# TVP5150AM1.net
KiCad netlist of a schematic drawn in Altium Designer
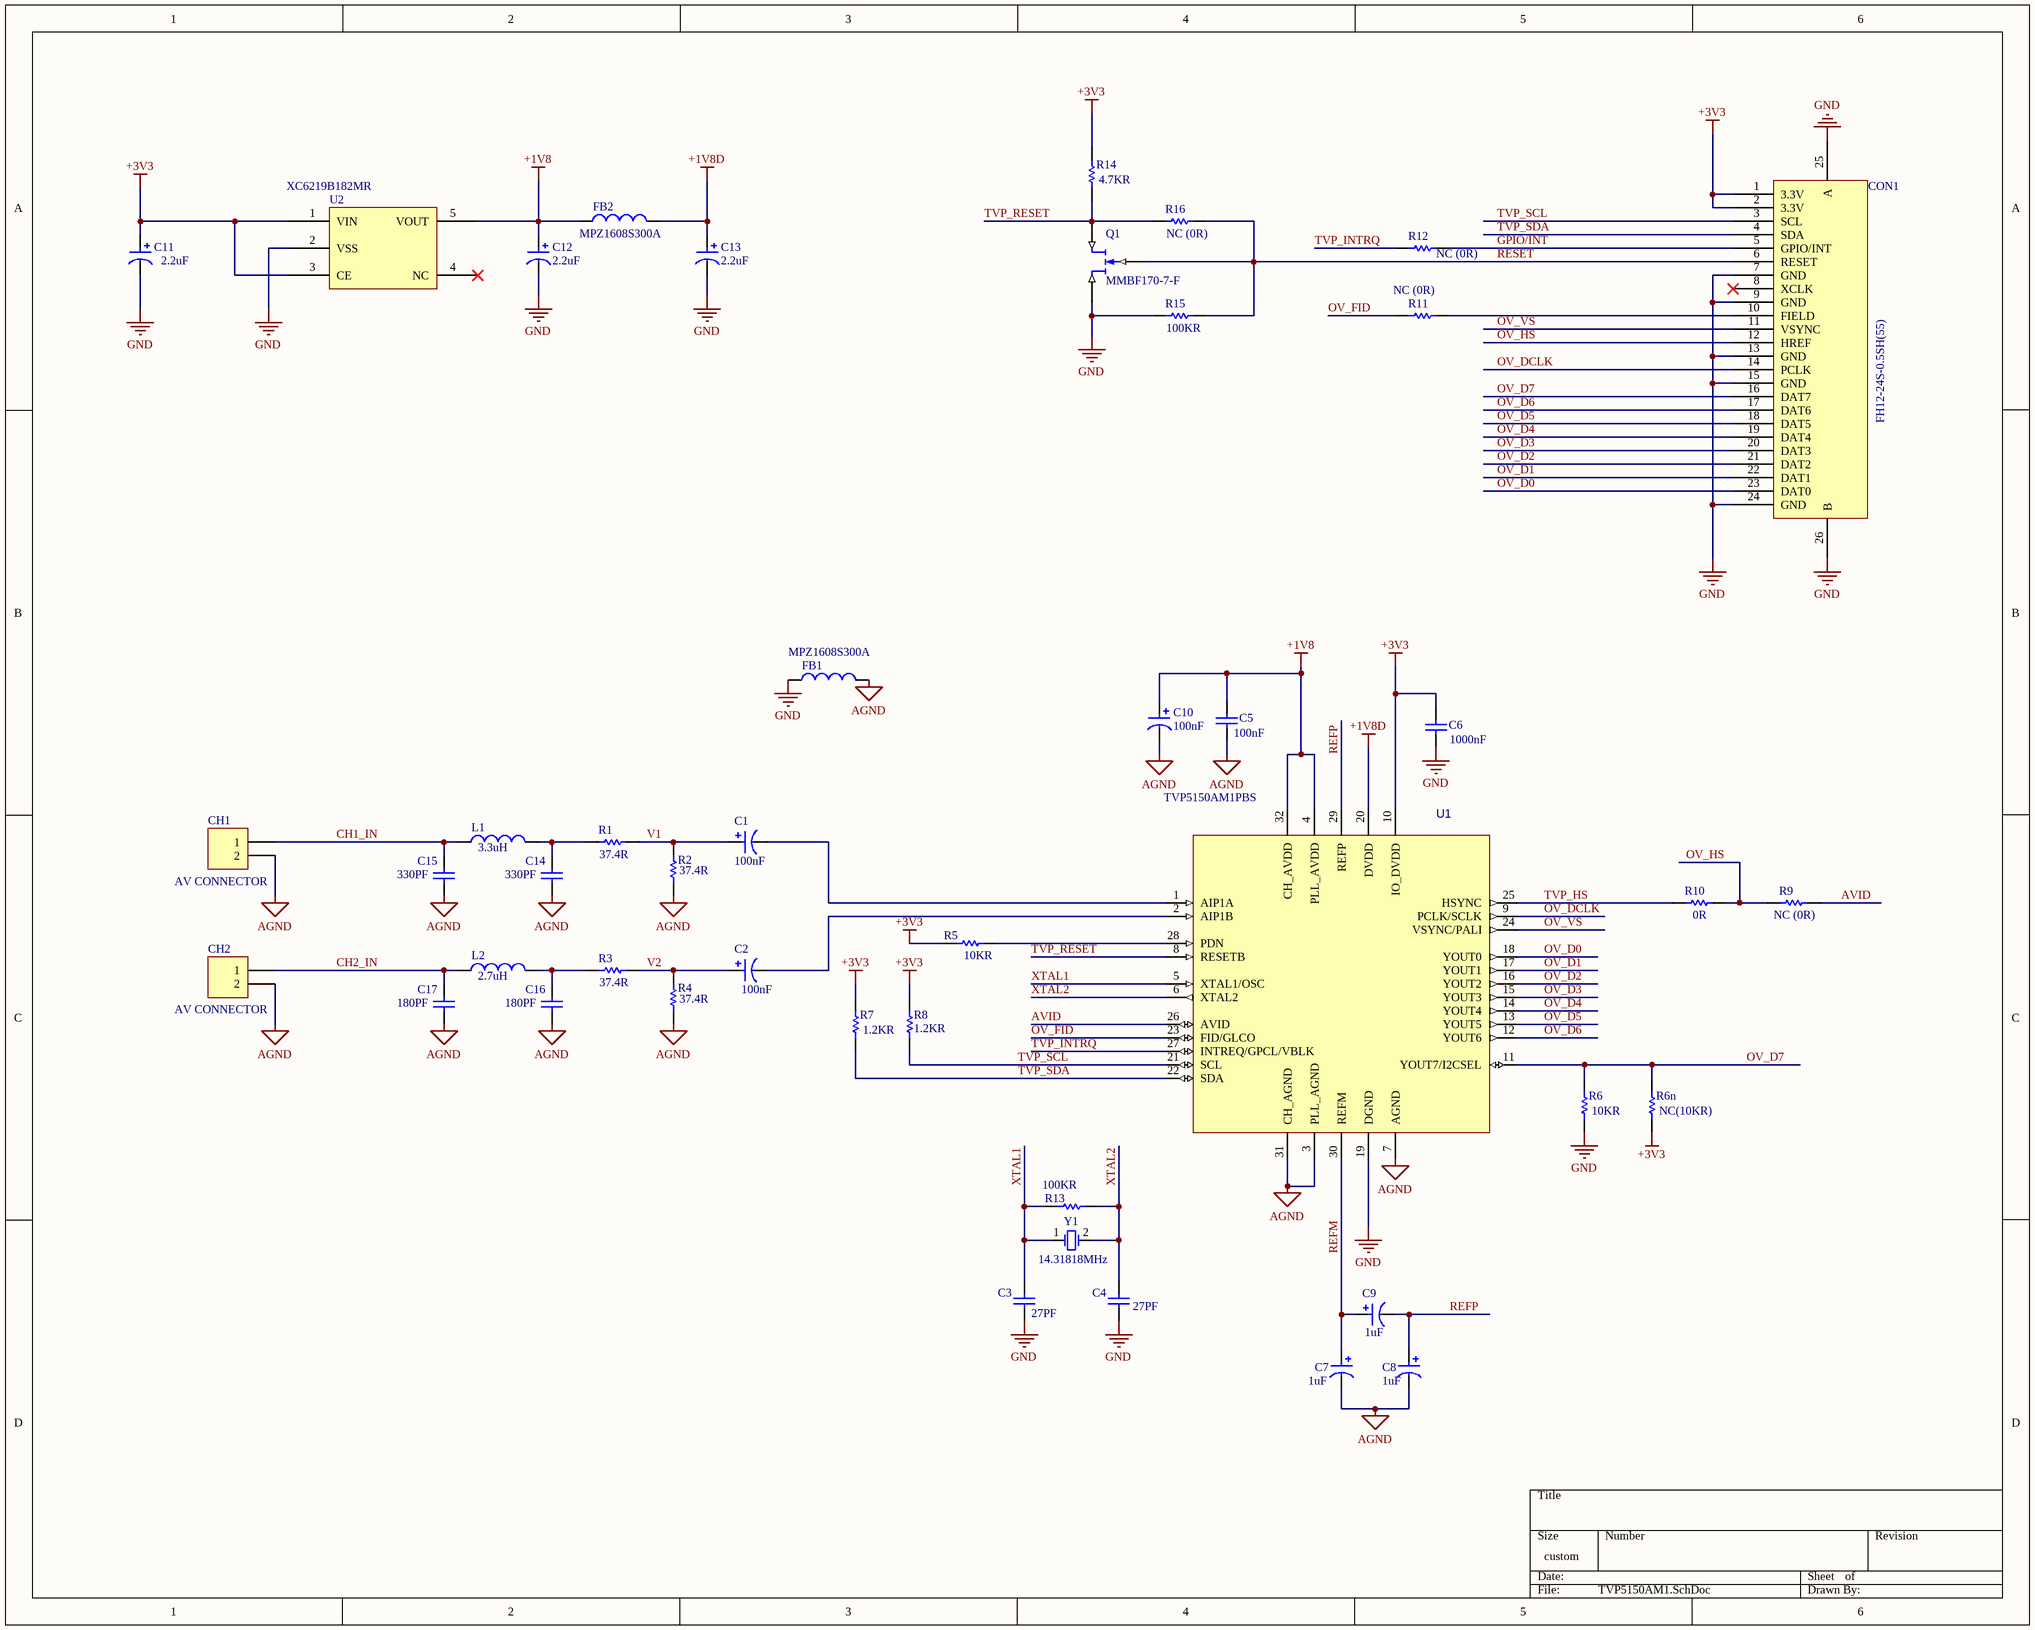
[diagram p0: TVP5150AM1.SchDoc]

(export (version "E")
  (design (tool "Eeschema 10.0.6"))
  (components
    (comp (ref "C1")
      (value "100nF")
      (footprint "C_1206 (3216 Metric)")
      (description "Chip Monolithic Ceramic Capacitor; SMD")
      (fields
        (field (name "MANUFACTURER") "Vishay or AVX Corporation")
        (field (name "PARTNUMBER") "100nF")
        (field (name "PUBLISHER") "Altium Limited")
      )
      (libsource (lib "Main_Lib") (part "Cap Pol SMD"))
    )
    (comp (ref "C2")
      (value "100nF")
      (footprint "C_1206 (3216 Metric)")
      (description "Chip Monolithic Ceramic Capacitor; SMD")
      (fields
        (field (name "MANUFACTURER") "Vishay or AVX Corporation")
        (field (name "PARTNUMBER") "100nF")
        (field (name "PUBLISHER") "Altium Limited")
      )
      (libsource (lib "Main_Lib") (part "Cap Pol SMD"))
    )
    (comp (ref "C3")
      (value "27PF")
      (footprint "C_0805 (2012 Metric)")
      (description "Chip Monolithic Ceramic Capacitor; SMD")
      (fields (field (name "PARTNUMBER") "27PF") (field (name "PUBLISHER") "Altium Limited"))
      (libsource (lib "Miscellaneous Devices") (part "Cap"))
    )
    (comp (ref "C4")
      (value "27PF")
      (footprint "C_0805 (2012 Metric)")
      (description "Chip Monolithic Ceramic Capacitor; SMD")
      (fields (field (name "PARTNUMBER") "27PF") (field (name "PUBLISHER") "Altium Limited"))
      (libsource (lib "Miscellaneous Devices") (part "Cap"))
    )
    (comp (ref "C5")
      (value "100nF")
      (footprint "C_0805 (2012 Metric)")
      (description "Chip Monolithic Ceramic Capacitor; SMD")
      (fields (field (name "PARTNUMBER") "100nF") (field (name "PUBLISHER") "Altium Limited"))
      (libsource (lib "Miscellaneous Devices") (part "Cap"))
    )
    (comp (ref "C6")
      (value "1000nF")
      (footprint "C_0805 (2012 Metric)")
      (description "Chip Monolithic Ceramic Capacitor; SMD")
      (fields (field (name "PARTNUMBER") "1000nF") (field (name "PUBLISHER") "Altium Limited"))
      (libsource (lib "Miscellaneous Devices") (part "Cap"))
    )
    (comp (ref "C7")
      (value "1uF")
      (footprint "C_1206 (3216 Metric)")
      (description "Chip Monolithic Ceramic Capacitor; SMD")
      (fields
        (field (name "MANUFACTURER") "Vishay or AVX Corporation")
        (field (name "PARTNUMBER") "1uF")
        (field (name "PUBLISHER") "Altium Limited")
      )
      (libsource (lib "") (part "Cap Pol SMD_1"))
    )
    (comp (ref "C8")
      (value "1uF")
      (footprint "C_1206 (3216 Metric)")
      (description "Chip Monolithic Ceramic Capacitor; SMD")
      (fields
        (field (name "MANUFACTURER") "Vishay or AVX Corporation")
        (field (name "PARTNUMBER") "1uF")
        (field (name "PUBLISHER") "Altium Limited")
      )
      (libsource (lib "") (part "Cap Pol SMD_1"))
    )
    (comp (ref "C9")
      (value "1uF")
      (footprint "C_1206 (3216 Metric)")
      (description "Chip Monolithic Ceramic Capacitor; SMD")
      (fields
        (field (name "MANUFACTURER") "Vishay or AVX Corporation")
        (field (name "PARTNUMBER") "1uF")
        (field (name "PUBLISHER") "Altium Limited")
      )
      (libsource (lib "Main_Lib") (part "Cap Pol SMD"))
    )
    (comp (ref "C10")
      (value "100nF")
      (footprint "C_1206 (3216 Metric)")
      (description "Chip Monolithic Ceramic Capacitor; SMD")
      (fields
        (field (name "MANUFACTURER") "Vishay or AVX Corporation")
        (field (name "PARTNUMBER") "100nF")
        (field (name "PUBLISHER") "Altium Limited")
      )
      (libsource (lib "") (part "Cap Pol SMD_1"))
    )
    (comp (ref "C11")
      (value "2.2uF")
      (footprint "Tantalum-A")
      (description "Tantalum SMD Capacitor")
      (fields
        (field (name "MANUFACTURER") "Vishay or AVX Corporation")
        (field (name "PARTNUMBER") "2.2uF")
        (field (name "PUBLISHER") "Altium Limited")
      )
      (libsource (lib "") (part "Cap Pol SMD_1"))
    )
    (comp (ref "C12")
      (value "2.2uF")
      (footprint "Tantalum-A")
      (description "Tantalum SMD Capacitor")
      (fields
        (field (name "MANUFACTURER") "Vishay or AVX Corporation")
        (field (name "PARTNUMBER") "2.2uF")
        (field (name "PUBLISHER") "Altium Limited")
      )
      (libsource (lib "") (part "Cap Pol SMD_1"))
    )
    (comp (ref "C13")
      (value "2.2uF")
      (footprint "Tantalum-A")
      (description "Tantalum SMD Capacitor")
      (fields
        (field (name "MANUFACTURER") "Vishay or AVX Corporation")
        (field (name "PART NUMBER") "2.2uF")
        (field (name "PUBLISHER") "Altium Limited")
      )
      (libsource (lib "") (part "Cap Pol SMD_1"))
    )
    (comp (ref "C14")
      (value "330PF")
      (footprint "C_0805 (2012 Metric)")
      (description "Chip Monolithic Ceramic Capacitor; SMD")
      (fields (field (name "PARTNUMBER") "330PF") (field (name "PUBLISHER") "Altium Limited"))
      (libsource (lib "Miscellaneous Devices") (part "Cap"))
    )
    (comp (ref "C15")
      (value "330PF")
      (footprint "C_0805 (2012 Metric)")
      (description "Chip Monolithic Ceramic Capacitor; SMD")
      (fields (field (name "PARTNUMBER") "330PF") (field (name "PUBLISHER") "Altium Limited"))
      (libsource (lib "Miscellaneous Devices") (part "Cap"))
    )
    (comp (ref "C16")
      (value "180PF")
      (footprint "C_0805 (2012 Metric)")
      (description "Chip Monolithic Ceramic Capacitor; SMD")
      (fields (field (name "PARTNUMBER") "180PF") (field (name "PUBLISHER") "Altium Limited"))
      (libsource (lib "Miscellaneous Devices") (part "Cap"))
    )
    (comp (ref "C17")
      (value "180PF")
      (footprint "C_0805 (2012 Metric)")
      (description "Chip Monolithic Ceramic Capacitor; SMD")
      (fields (field (name "PARTNUMBER") "180PF") (field (name "PUBLISHER") "Altium Limited"))
      (libsource (lib "Miscellaneous Devices") (part "Cap"))
    )
    (comp (ref "CH1")
      (value "AV CONNECTOR")
      (footprint "RCA-CONN")
      (description "Header, 2-Pin")
      (fields (field (name "PARTNUMBER") "AV CONNECTOR") (field (name "PUBLISHER") "Altium Limited"))
      (libsource (lib "Miscellaneous Connectors") (part "Header 2"))
    )
    (comp (ref "CH2")
      (value "AV CONNECTOR")
      (footprint "RCA-CONN")
      (description "Header, 2-Pin")
      (fields (field (name "PARTNUMBER") "AV CONNECTOR") (field (name "PUBLISHER") "Altium Limited"))
      (libsource (lib "Miscellaneous Connectors") (part "Header 2"))
    )
    (comp (ref "CON1")
      (value "24 PIN FFC CONNECTOR 0.5MM PITCH")
      (footprint "FH12-24S-0.5SH")
      (description "CONN FFC BOTTOM 24POS 0.50MM R/A")
      (fields
        (field (name "MANUFACTURER") "Hirose Electric Co Ltd")
        (field (name "MANUFACTURER PART NUMBER") "FH12-24S-0.5SH(55)")
        (field (name "PARTNUMBER") "FH12-24S-0.5SH(55)")
      )
      (libsource (lib "TVP5150AM1") (part "CSI DVP CAMERA CONNECTOR"))
    )
    (comp (ref "FB1")
      (value "MPZ1608S300A")
      (footprint "L_0805 (2012 Metric)")
      (description "FERRITE BEAD 30 OHM 0603 1LN")
      (fields
        (field (name "PARTNUMBER") "MPZ1608S300A")
        (field (name "MANUFACTURER PART NUMBER") "MPZ1608S300ATAH0")
        (field (name "PUBLISHER") "Altium Limited")
      )
      (libsource (lib "Main_Lib") (part "Inductor"))
    )
    (comp (ref "FB2")
      (value "MPZ1608S300A")
      (footprint "L_0805 (2012 Metric)")
      (description "FERRITE BEAD 30 OHM 0603 1LN")
      (fields
        (field (name "PARTNUMBER") "MPZ1608S300A")
        (field (name "MANUFACTURER PART NUMBER") "MPZ1608S300ATAH0")
        (field (name "PUBLISHER") "Altium Limited")
      )
      (libsource (lib "Main_Lib") (part "Inductor"))
    )
    (comp (ref "L1")
      (value "3.3uH")
      (footprint "L_0805 (2012 Metric)")
      (description "FIXED IND 3.3UH 750MA 300 MOHM SMD")
      (fields (field (name "PARTNUMBER") "3.3uH") (field (name "PUBLISHER") "Altium Limited"))
      (libsource (lib "Main_Lib") (part "Inductor"))
    )
    (comp (ref "L2")
      (value "2.7uH")
      (footprint "L_0805 (2012 Metric)")
      (description "FIXED IND 2.7UH 750MA 300 MOHM SMD")
      (fields (field (name "PARTNUMBER") "2.7uH") (field (name "PUBLISHER") "Altium Limited"))
      (libsource (lib "Main_Lib") (part "Inductor"))
    )
    (comp (ref "Q1")
      (value "MMBF170-7-F")
      (footprint "SOT-23-3")
      (description "MOSFET N-CH 60V 500MA SOT23-3")
      (fields (field (name "MANUFACTURER") "Diodes Incorporated") (field (name "PARTNUMBER") "MMBF170-7-F"))
      (libsource (lib "Miscellaneous Devices") (part "MESFET-N"))
    )
    (comp (ref "R1")
      (value "37.4R")
      (footprint "R_0805 (2012 Metric)")
      (description "Resistor")
      (fields (field (name "PARTNUMBER") "37.4R") (field (name "PUBLISHER") "Altium Limited"))
      (libsource (lib "Miscellaneous Devices") (part "Res1"))
    )
    (comp (ref "R2")
      (value "37.4R")
      (footprint "R_0805 (2012 Metric)")
      (description "Resistor")
      (fields (field (name "PARTNUMBER") "37.4R") (field (name "PUBLISHER") "Altium Limited"))
      (libsource (lib "Miscellaneous Devices") (part "Res1"))
    )
    (comp (ref "R3")
      (value "37.4R")
      (footprint "R_0805 (2012 Metric)")
      (description "Resistor")
      (fields (field (name "PARTNUMBER") "37.4R") (field (name "PUBLISHER") "Altium Limited"))
      (libsource (lib "Miscellaneous Devices") (part "Res1"))
    )
    (comp (ref "R4")
      (value "37.4R")
      (footprint "R_0805 (2012 Metric)")
      (description "Resistor")
      (fields (field (name "PARTNUMBER") "37.4R") (field (name "PUBLISHER") "Altium Limited"))
      (libsource (lib "Miscellaneous Devices") (part "Res1"))
    )
    (comp (ref "R5")
      (value "10KR")
      (footprint "R_0805 (2012 Metric)")
      (description "Resistor")
      (fields (field (name "PARTNUMBER") "10KR") (field (name "PUBLISHER") "Altium Limited"))
      (libsource (lib "Miscellaneous Devices") (part "Res1"))
    )
    (comp (ref "R6")
      (value "10KR")
      (footprint "R_0805 (2012 Metric)")
      (description "Resistor")
      (fields (field (name "PARTNUMBER") "10KR") (field (name "PUBLISHER") "Altium Limited"))
      (libsource (lib "Miscellaneous Devices") (part "Res1"))
    )
    (comp (ref "R6n")
      (value "NC(10KR)")
      (footprint "R_0805 (2012 Metric)")
      (description "Resistor")
      (fields (field (name "PARTNUMBER") "NC(10KR)") (field (name "PUBLISHER") "Altium Limited"))
      (libsource (lib "Miscellaneous Devices") (part "Res1"))
    )
    (comp (ref "R7")
      (value "1.2KR")
      (footprint "R_0805 (2012 Metric)")
      (description "Resistor")
      (fields (field (name "PARTNUMBER") "1.2KR") (field (name "PUBLISHER") "Altium Limited"))
      (libsource (lib "Miscellaneous Devices") (part "Res1"))
    )
    (comp (ref "R8")
      (value "1.2KR")
      (footprint "R_0805 (2012 Metric)")
      (description "Resistor")
      (fields (field (name "PARTNUMBER") "1.2KR") (field (name "PUBLISHER") "Altium Limited"))
      (libsource (lib "Miscellaneous Devices") (part "Res1"))
    )
    (comp (ref "R9")
      (value "NC (0R)")
      (footprint "R_0805 (2012 Metric)")
      (description "Resistor")
      (fields (field (name "PARTNUMBER") "NC (0R)") (field (name "PUBLISHER") "Altium Limited"))
      (libsource (lib "Miscellaneous Devices") (part "Res1"))
    )
    (comp (ref "R10")
      (value "0R")
      (footprint "R_0805 (2012 Metric)")
      (description "Resistor")
      (fields (field (name "PARTNUMBER") "0R") (field (name "PUBLISHER") "Altium Limited"))
      (libsource (lib "Miscellaneous Devices") (part "Res1"))
    )
    (comp (ref "R11")
      (value "NC (0R)")
      (footprint "R_0805 (2012 Metric)")
      (description "Resistor")
      (fields (field (name "PARTNUMBER") "NC (0R)") (field (name "PUBLISHER") "Altium Limited"))
      (libsource (lib "Miscellaneous Devices") (part "Res1"))
    )
    (comp (ref "R12")
      (value "NC (0R)")
      (footprint "R_0805 (2012 Metric)")
      (description "Resistor")
      (fields (field (name "PARTNUMBER") "NC (0R)") (field (name "PUBLISHER") "Altium Limited"))
      (libsource (lib "Miscellaneous Devices") (part "Res1"))
    )
    (comp (ref "R13")
      (value "100KR")
      (footprint "R_0805 (2012 Metric)")
      (description "Resistor")
      (fields (field (name "PARTNUMBER") "100KR") (field (name "PUBLISHER") "Altium Limited"))
      (libsource (lib "Miscellaneous Devices") (part "Res1"))
    )
    (comp (ref "R14")
      (value "4.7KR")
      (footprint "R_0805 (2012 Metric)")
      (description "Resistor")
      (fields (field (name "PARTNUMBER") "4.7KR") (field (name "PUBLISHER") "Altium Limited"))
      (libsource (lib "Miscellaneous Devices") (part "Res1"))
    )
    (comp (ref "R15")
      (value "100KR")
      (footprint "R_0805 (2012 Metric)")
      (description "Resistor")
      (fields (field (name "PARTNUMBER") "100KR") (field (name "PUBLISHER") "Altium Limited"))
      (libsource (lib "Miscellaneous Devices") (part "Res1"))
    )
    (comp (ref "R16")
      (value "NC (0R)")
      (footprint "R_0805 (2012 Metric)")
      (description "Resistor")
      (fields (field (name "PARTNUMBER") "NC (0R)") (field (name "PUBLISHER") "Altium Limited"))
      (libsource (lib "Miscellaneous Devices") (part "Res1"))
    )
    (comp (ref "U1")
      (value "TVP5150AM1PBS")
      (footprint "PBS32")
      (description "Ultralow Power NTSC/PAL/SECAM 9-Bit Video Decoder with Robust Sync Detector, 32-Pin TQFP")
      (fields (field (name "PARTNUMBER") "TVP5150AM1PBS") (field (name "PUBLISHER") "Altium Limited"))
      (libsource (lib "TI Video Colour Decoder Circuit") (part "TVP5150AM1PBS"))
    )
    (comp (ref "U2")
      (value "XC6219B182MR")
      (footprint "SOT23-5")
      (description "300mA High Speed LDO Regulators with ON/OFF Switch")
      (fields (field (name "PARTNUMBER") "XC6219B182MR"))
      (libsource (lib "TVP5150AM1") (part "XC6219B182MR"))
    )
    (comp (ref "Y1")
      (value "14.31818MHz")
      (footprint "XTAL_S")
      (description "CRYSTAL 14.7456MHZ 18PF THRU")
      (fields
        (field (name "MANUFACTURER") "TXC CORPORATION")
        (field (name "PARTNUMBER") "14.31818MHz")
        (field (name "PUBLISHER") "Altium Limited")
      )
      (libsource (lib "Main_Lib") (part "XTAL"))
    )
  )
  (nets
    (net (code "1") (name "+1V8") (class "Default")
      (node (ref "C10") (pin "1") (pinfunction "1_1") (pintype "passive"))
      (node (ref "C12") (pin "1") (pinfunction "1_1") (pintype "passive"))
      (node (ref "C5") (pin "1") (pinfunction "1_1") (pintype "passive"))
      (node (ref "FB2") (pin "1") (pinfunction "1_1") (pintype "passive"))
      (node (ref "U1") (pin "32") (pinfunction "CH_AVDD_32") (pintype "power_in"))
      (node (ref "U1") (pin "4") (pinfunction "PLL_AVDD_4") (pintype "power_in"))
      (node (ref "U2") (pin "5") (pinfunction "VOUT_5") (pintype "passive"))
    )
    (net (code "2") (name "+1V8D") (class "Default")
      (node (ref "C13") (pin "1") (pinfunction "1_1") (pintype "passive"))
      (node (ref "FB2") (pin "2") (pinfunction "2_2") (pintype "passive"))
      (node (ref "U1") (pin "20") (pinfunction "DVDD_20") (pintype "power_in"))
    )
    (net (code "3") (name "+3V3") (class "Default")
      (node (ref "C11") (pin "1") (pinfunction "1_1") (pintype "passive"))
      (node (ref "C6") (pin "1") (pinfunction "1_1") (pintype "passive"))
      (node (ref "CON1") (pin "1") (pinfunction "3.3V_1") (pintype "passive"))
      (node (ref "CON1") (pin "2") (pinfunction "3.3V_2") (pintype "passive"))
      (node (ref "R14") (pin "1") (pinfunction "1_1") (pintype "passive"))
      (node (ref "R5") (pin "2") (pinfunction "2_2") (pintype "passive"))
      (node (ref "R6n") (pin "2") (pinfunction "2_2") (pintype "passive"))
      (node (ref "R7") (pin "1") (pinfunction "1_1") (pintype "passive"))
      (node (ref "R8") (pin "1") (pinfunction "1_1") (pintype "passive"))
      (node (ref "U1") (pin "10") (pinfunction "IO_DVDD_10") (pintype "power_in"))
      (node (ref "U2") (pin "1") (pinfunction "VIN_1") (pintype "passive"))
      (node (ref "U2") (pin "3") (pinfunction "CE_3") (pintype "passive"))
    )
    (net (code "4") (name "/AVID") (class "Default")
      (node (ref "R9") (pin "2") (pinfunction "2_2") (pintype "passive"))
      (node (ref "U1") (pin "26") (pinfunction "AVID_26") (pintype "bidirectional"))
    )
    (net (code "5") (name "/CH1_IN") (class "Default")
      (node (ref "C15") (pin "2") (pinfunction "2_2") (pintype "passive"))
      (node (ref "CH1") (pin "1") (pinfunction "1_1") (pintype "passive"))
      (node (ref "L1") (pin "1") (pinfunction "1_1") (pintype "passive"))
    )
    (net (code "6") (name "/CH2_IN") (class "Default")
      (node (ref "C17") (pin "2") (pinfunction "2_2") (pintype "passive"))
      (node (ref "CH2") (pin "1") (pinfunction "1_1") (pintype "passive"))
      (node (ref "L2") (pin "1") (pinfunction "1_1") (pintype "passive"))
    )
    (net (code "7") (name "/GPIO{slash}INT") (class "Default")
      (node (ref "CON1") (pin "5") (pinfunction "GPIO/INT_5") (pintype "passive"))
      (node (ref "R12") (pin "2") (pinfunction "2_2") (pintype "passive"))
    )
    (net (code "8") (name "/OV_D0") (class "Default")
      (node (ref "CON1") (pin "23") (pinfunction "DAT0_23") (pintype "passive"))
      (node (ref "U1") (pin "18") (pinfunction "YOUT0_18") (pintype "output"))
    )
    (net (code "9") (name "/OV_D1") (class "Default")
      (node (ref "CON1") (pin "22") (pinfunction "DAT1_22") (pintype "passive"))
      (node (ref "U1") (pin "17") (pinfunction "YOUT1_17") (pintype "output"))
    )
    (net (code "10") (name "/OV_D2") (class "Default")
      (node (ref "CON1") (pin "21") (pinfunction "DAT2_21") (pintype "passive"))
      (node (ref "U1") (pin "16") (pinfunction "YOUT2_16") (pintype "output"))
    )
    (net (code "11") (name "/OV_D3") (class "Default")
      (node (ref "CON1") (pin "20") (pinfunction "DAT3_20") (pintype "passive"))
      (node (ref "U1") (pin "15") (pinfunction "YOUT3_15") (pintype "output"))
    )
    (net (code "12") (name "/OV_D4") (class "Default")
      (node (ref "CON1") (pin "19") (pinfunction "DAT4_19") (pintype "passive"))
      (node (ref "U1") (pin "14") (pinfunction "YOUT4_14") (pintype "output"))
    )
    (net (code "13") (name "/OV_D5") (class "Default")
      (node (ref "CON1") (pin "18") (pinfunction "DAT5_18") (pintype "passive"))
      (node (ref "U1") (pin "13") (pinfunction "YOUT5_13") (pintype "output"))
    )
    (net (code "14") (name "/OV_D6") (class "Default")
      (node (ref "CON1") (pin "17") (pinfunction "DAT6_17") (pintype "passive"))
      (node (ref "U1") (pin "12") (pinfunction "YOUT6_12") (pintype "output"))
    )
    (net (code "15") (name "/OV_D7") (class "Default")
      (node (ref "CON1") (pin "16") (pinfunction "DAT7_16") (pintype "passive"))
      (node (ref "R6") (pin "1") (pinfunction "1_1") (pintype "passive"))
      (node (ref "R6n") (pin "1") (pinfunction "1_1") (pintype "passive"))
      (node (ref "U1") (pin "11") (pinfunction "YOUT7/I2CSEL_11") (pintype "bidirectional"))
    )
    (net (code "16") (name "/OV_DCLK") (class "Default")
      (node (ref "CON1") (pin "14") (pinfunction "PCLK_14") (pintype "passive"))
      (node (ref "U1") (pin "9") (pinfunction "PCLK/SCLK_9") (pintype "output"))
    )
    (net (code "17") (name "/OV_FID") (class "Default")
      (node (ref "R11") (pin "1") (pinfunction "1_1") (pintype "passive"))
      (node (ref "U1") (pin "23") (pinfunction "FID/GLCO_23") (pintype "bidirectional"))
    )
    (net (code "18") (name "/OV_HS") (class "Default")
      (node (ref "CON1") (pin "12") (pinfunction "HREF_12") (pintype "passive"))
      (node (ref "R10") (pin "2") (pinfunction "2_2") (pintype "passive"))
      (node (ref "R9") (pin "1") (pinfunction "1_1") (pintype "passive"))
    )
    (net (code "19") (name "/OV_VS") (class "Default")
      (node (ref "CON1") (pin "11") (pinfunction "VSYNC_11") (pintype "passive"))
      (node (ref "U1") (pin "24") (pinfunction "VSYNC/PALI_24") (pintype "output"))
    )
    (net (code "20") (name "/REFM") (class "Default")
      (node (ref "C7") (pin "1") (pinfunction "1_1") (pintype "passive"))
      (node (ref "C9") (pin "1") (pinfunction "1_1") (pintype "passive"))
      (node (ref "U1") (pin "30") (pinfunction "REFM_30") (pintype "power_in"))
    )
    (net (code "21") (name "/REFP") (class "Default")
      (node (ref "C8") (pin "1") (pinfunction "1_1") (pintype "passive"))
      (node (ref "C9") (pin "2") (pinfunction "2_2") (pintype "passive"))
      (node (ref "U1") (pin "29") (pinfunction "REFP_29") (pintype "power_in"))
    )
    (net (code "22") (name "/RESET") (class "Default")
      (node (ref "CON1") (pin "6") (pinfunction "RESET_6") (pintype "passive"))
      (node (ref "Q1") (pin "1") (pinfunction "G_1") (pintype "input"))
      (node (ref "R15") (pin "2") (pinfunction "2_2") (pintype "passive"))
      (node (ref "R16") (pin "2") (pinfunction "2_2") (pintype "passive"))
    )
    (net (code "23") (name "/TVP_HS") (class "Default")
      (node (ref "R10") (pin "1") (pinfunction "1_1") (pintype "passive"))
      (node (ref "U1") (pin "25") (pinfunction "HSYNC_25") (pintype "output"))
    )
    (net (code "24") (name "/TVP_INTRQ") (class "Default")
      (node (ref "R12") (pin "1") (pinfunction "1_1") (pintype "passive"))
      (node (ref "U1") (pin "27") (pinfunction "INTREQ/GPCL/VBLK_27") (pintype "bidirectional"))
    )
    (net (code "25") (name "/TVP_RESET") (class "Default")
      (node (ref "Q1") (pin "3") (pinfunction "D_3") (pintype "input"))
      (node (ref "R14") (pin "2") (pinfunction "2_2") (pintype "passive"))
      (node (ref "R16") (pin "1") (pinfunction "1_1") (pintype "passive"))
      (node (ref "U1") (pin "8") (pinfunction "RESETB_8") (pintype "input"))
    )
    (net (code "26") (name "/TVP_SCL") (class "Default")
      (node (ref "CON1") (pin "3") (pinfunction "SCL_3") (pintype "passive"))
      (node (ref "R8") (pin "2") (pinfunction "2_2") (pintype "passive"))
      (node (ref "U1") (pin "21") (pinfunction "SCL_21") (pintype "bidirectional"))
    )
    (net (code "27") (name "/TVP_SDA") (class "Default")
      (node (ref "CON1") (pin "4") (pinfunction "SDA_4") (pintype "passive"))
      (node (ref "R7") (pin "2") (pinfunction "2_2") (pintype "passive"))
      (node (ref "U1") (pin "22") (pinfunction "SDA_22") (pintype "bidirectional"))
    )
    (net (code "28") (name "/V1") (class "Default")
      (node (ref "C1") (pin "1") (pinfunction "1_1") (pintype "passive"))
      (node (ref "R1") (pin "2") (pinfunction "2_2") (pintype "passive"))
      (node (ref "R2") (pin "1") (pinfunction "1_1") (pintype "passive"))
    )
    (net (code "29") (name "/V2") (class "Default")
      (node (ref "C2") (pin "1") (pinfunction "1_1") (pintype "passive"))
      (node (ref "R3") (pin "2") (pinfunction "2_2") (pintype "passive"))
      (node (ref "R4") (pin "1") (pinfunction "1_1") (pintype "passive"))
    )
    (net (code "30") (name "/XTAL1") (class "Default")
      (node (ref "C3") (pin "2") (pinfunction "2_2") (pintype "passive"))
      (node (ref "R13") (pin "2") (pinfunction "2_2") (pintype "passive"))
      (node (ref "U1") (pin "5") (pinfunction "XTAL1/OSC_5") (pintype "input"))
      (node (ref "Y1") (pin "1") (pinfunction "OSC1_1") (pintype "passive"))
    )
    (net (code "31") (name "/XTAL2") (class "Default")
      (node (ref "C4") (pin "2") (pinfunction "2_2") (pintype "passive"))
      (node (ref "R13") (pin "1") (pinfunction "1_1") (pintype "passive"))
      (node (ref "U1") (pin "6") (pinfunction "XTAL2_6") (pintype "output"))
      (node (ref "Y1") (pin "2") (pinfunction "OSC2_2") (pintype "passive"))
    )
    (net (code "32") (name "AGND") (class "Default")
      (node (ref "C10") (pin "2") (pinfunction "2_2") (pintype "passive"))
      (node (ref "C14") (pin "1") (pinfunction "1_1") (pintype "passive"))
      (node (ref "C15") (pin "1") (pinfunction "1_1") (pintype "passive"))
      (node (ref "C16") (pin "1") (pinfunction "1_1") (pintype "passive"))
      (node (ref "C17") (pin "1") (pinfunction "1_1") (pintype "passive"))
      (node (ref "C5") (pin "2") (pinfunction "2_2") (pintype "passive"))
      (node (ref "C7") (pin "2") (pinfunction "2_2") (pintype "passive"))
      (node (ref "C8") (pin "2") (pinfunction "2_2") (pintype "passive"))
      (node (ref "CH1") (pin "2") (pinfunction "2_2") (pintype "passive"))
      (node (ref "CH2") (pin "2") (pinfunction "2_2") (pintype "passive"))
      (node (ref "FB1") (pin "2") (pinfunction "2_2") (pintype "passive"))
      (node (ref "R2") (pin "2") (pinfunction "2_2") (pintype "passive"))
      (node (ref "R4") (pin "2") (pinfunction "2_2") (pintype "passive"))
      (node (ref "U1") (pin "3") (pinfunction "PLL_AGND_3") (pintype "power_in"))
      (node (ref "U1") (pin "31") (pinfunction "CH_AGND_31") (pintype "power_in"))
      (node (ref "U1") (pin "7") (pinfunction "AGND_7") (pintype "passive"))
    )
    (net (code "33") (name "GND") (class "Default")
      (node (ref "C11") (pin "2") (pinfunction "2_2") (pintype "passive"))
      (node (ref "C12") (pin "2") (pinfunction "2_2") (pintype "passive"))
      (node (ref "C13") (pin "2") (pinfunction "2_2") (pintype "passive"))
      (node (ref "C3") (pin "1") (pinfunction "1_1") (pintype "passive"))
      (node (ref "C4") (pin "1") (pinfunction "1_1") (pintype "passive"))
      (node (ref "C6") (pin "2") (pinfunction "2_2") (pintype "passive"))
      (node (ref "CON1") (pin "13") (pinfunction "GND_13") (pintype "passive"))
      (node (ref "CON1") (pin "15") (pinfunction "GND_15") (pintype "passive"))
      (node (ref "CON1") (pin "24") (pinfunction "GND_24") (pintype "passive"))
      (node (ref "CON1") (pin "25") (pinfunction "A_25") (pintype "passive"))
      (node (ref "CON1") (pin "26") (pinfunction "B_26") (pintype "passive"))
      (node (ref "CON1") (pin "7") (pinfunction "GND_7") (pintype "passive"))
      (node (ref "CON1") (pin "9") (pinfunction "GND_9") (pintype "passive"))
      (node (ref "FB1") (pin "1") (pinfunction "1_1") (pintype "passive"))
      (node (ref "Q1") (pin "2") (pinfunction "S_2") (pintype "input"))
      (node (ref "R15") (pin "1") (pinfunction "1_1") (pintype "passive"))
      (node (ref "R6") (pin "2") (pinfunction "2_2") (pintype "passive"))
      (node (ref "U1") (pin "19") (pinfunction "DGND_19") (pintype "power_in"))
      (node (ref "U2") (pin "2") (pinfunction "VSS_2") (pintype "passive"))
    )
    (net (code "34") (name "Net-(C14-Pad2)") (class "Default")
      (node (ref "C14") (pin "2") (pinfunction "2_2") (pintype "passive"))
      (node (ref "L1") (pin "2") (pinfunction "2_2") (pintype "passive"))
      (node (ref "R1") (pin "1") (pinfunction "1_1") (pintype "passive"))
    )
    (net (code "35") (name "Net-(C16-Pad2)") (class "Default")
      (node (ref "C16") (pin "2") (pinfunction "2_2") (pintype "passive"))
      (node (ref "L2") (pin "2") (pinfunction "2_2") (pintype "passive"))
      (node (ref "R3") (pin "1") (pinfunction "1_1") (pintype "passive"))
    )
    (net (code "36") (name "Net-(CON1-FIELD)") (class "Default")
      (node (ref "CON1") (pin "10") (pinfunction "FIELD_10") (pintype "passive"))
      (node (ref "R11") (pin "2") (pinfunction "2_2") (pintype "passive"))
    )
    (net (code "37") (name "Net-(U1-AIP1A)") (class "Default")
      (node (ref "C1") (pin "2") (pinfunction "2_2") (pintype "passive"))
      (node (ref "U1") (pin "1") (pinfunction "AIP1A_1") (pintype "input"))
    )
    (net (code "38") (name "Net-(U1-AIP1B)") (class "Default")
      (node (ref "C2") (pin "2") (pinfunction "2_2") (pintype "passive"))
      (node (ref "U1") (pin "2") (pinfunction "AIP1B_2") (pintype "input"))
    )
    (net (code "39") (name "Net-(U1-PDN)") (class "Default")
      (node (ref "R5") (pin "1") (pinfunction "1_1") (pintype "passive"))
      (node (ref "U1") (pin "28") (pinfunction "PDN_28") (pintype "input"))
    )
    (net (code "40") (name "unconnected-(CON1-XCLK-Pad8)") (class "Default")
      (node (ref "CON1") (pin "8") (pinfunction "XCLK_8") (pintype "passive+no_connect"))
    )
    (net (code "41") (name "unconnected-(U2-NC-Pad4)") (class "Default")
      (node (ref "U2") (pin "4") (pinfunction "NC_4") (pintype "passive+no_connect"))
    )
  )
)
